# ESL_EMITTER.net
KiCad netlist of a schematic drawn in EAGLE
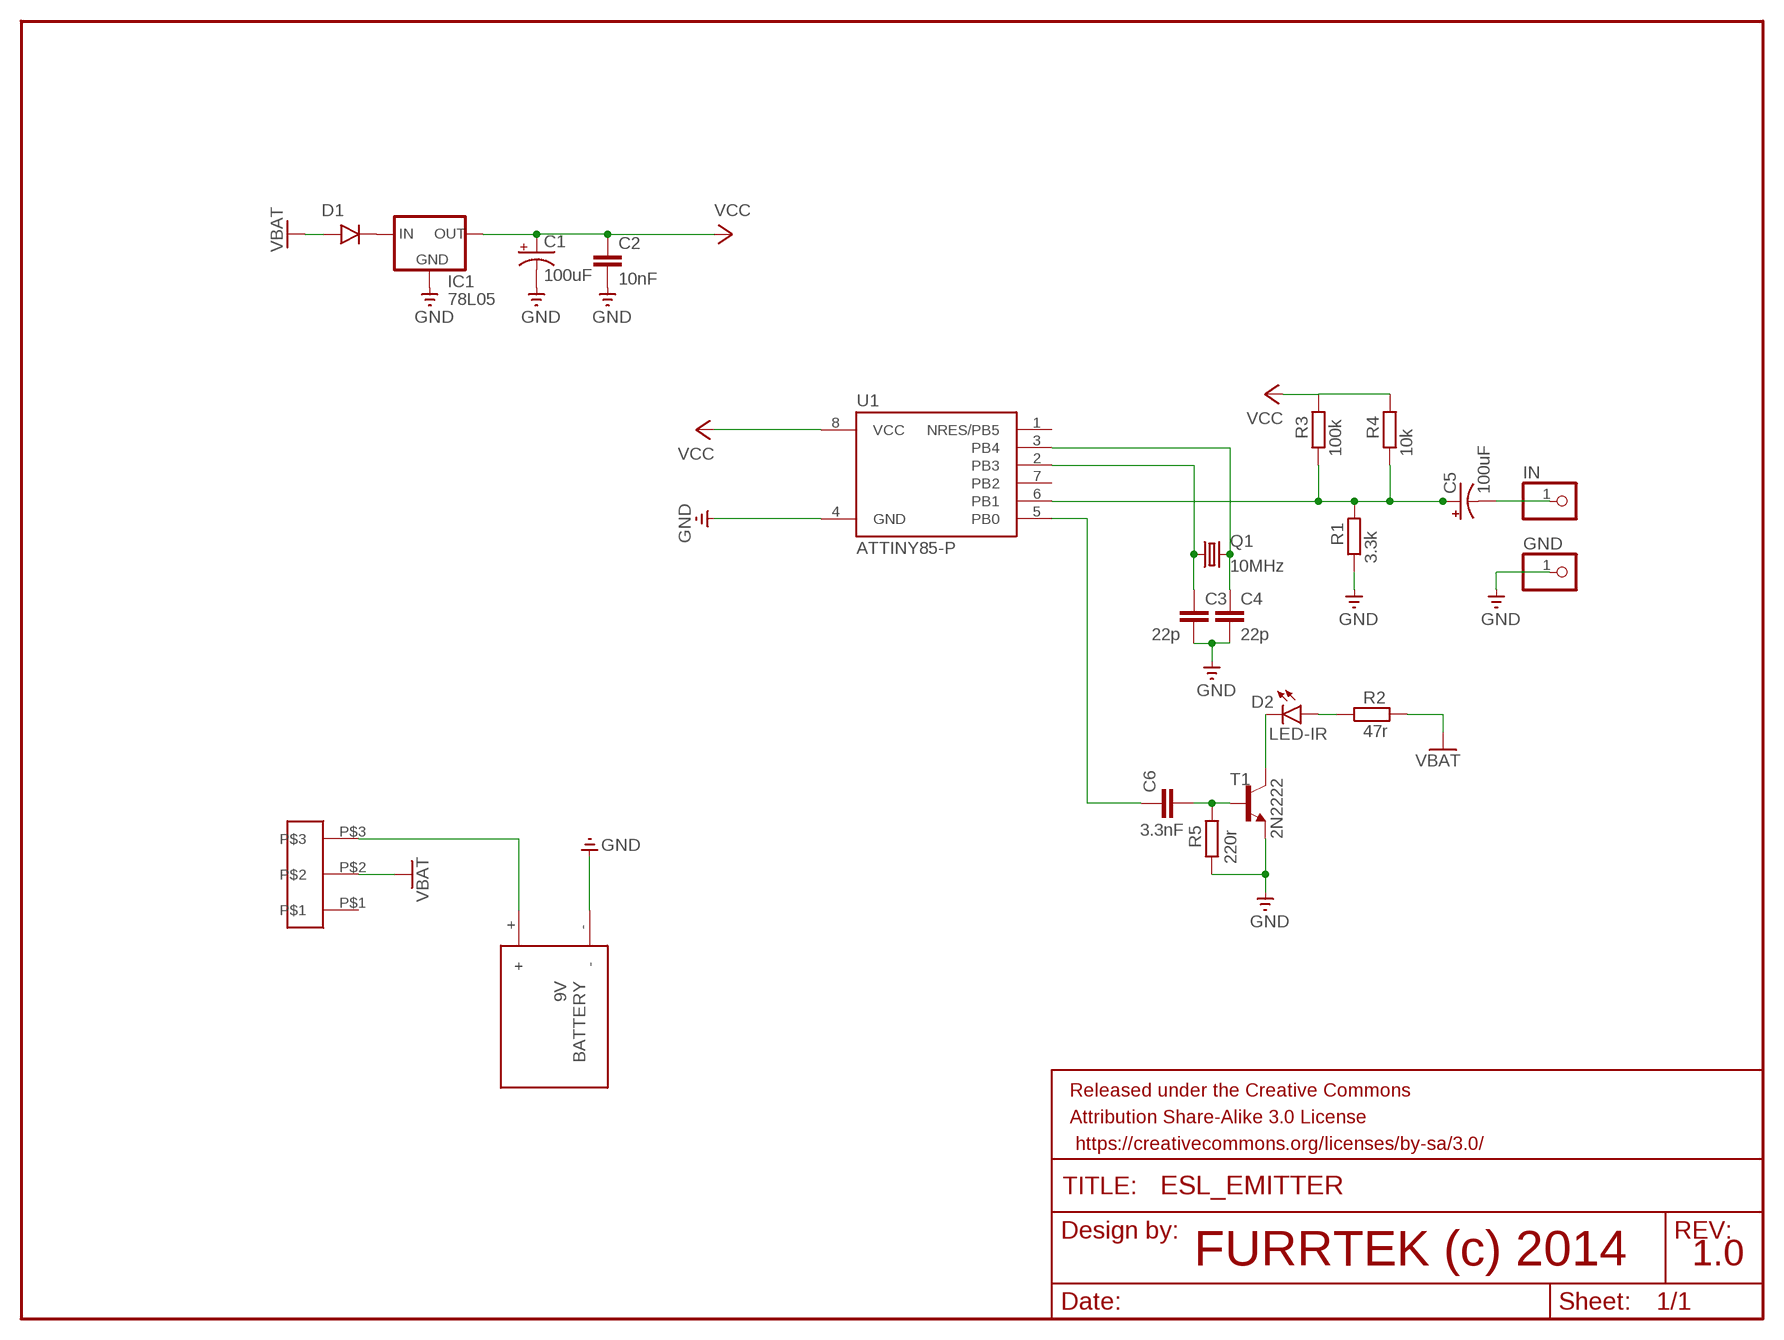
[diagram p0: schematic, sheet 1]

(export (version "E")
  (design (tool "Eeschema 10.0.6"))
  (components
    (comp (ref "C1")
      (value "100uF")
      (footprint "eagle-import:CPOL-RADIAL-10UF-25V")
      (libsource (lib "eagle-import") (part "CAP_POLPTH2"))
    )
    (comp (ref "C2")
      (value "10nF")
      (footprint "eagle-import:CAP-PTH-10MM")
      (libsource (lib "eagle-import") (part "10NF-PTH-10MM-10000V-1-%"))
    )
    (comp (ref "C3")
      (value "22p")
      (footprint "eagle-import:CAP-PTH-10MM")
      (libsource (lib "eagle-import") (part "10NF-PTH-10MM-10000V-1-%"))
    )
    (comp (ref "C4")
      (value "22p")
      (footprint "eagle-import:CAP-PTH-10MM")
      (libsource (lib "eagle-import") (part "10NF-PTH-10MM-10000V-1-%"))
    )
    (comp (ref "C5")
      (value "100uF")
      (footprint "eagle-import:CPOL-RADIAL-10UF-25V")
      (libsource (lib "eagle-import") (part "CAP_POLPTH2"))
    )
    (comp (ref "C6")
      (value "3.3nF")
      (footprint "eagle-import:CAP-PTH-10MM")
      (libsource (lib "eagle-import") (part "10NF-PTH-10MM-10000V-1-%"))
    )
    (comp (ref "D1")
      (value "1N4001")
      (footprint "eagle-import:DO41-10")
      (libsource (lib "eagle-import") (part "1N4001"))
    )
    (comp (ref "D2")
      (value "LED-IR")
      (footprint "eagle-import:LED_3MM-NS")
      (libsource (lib "eagle-import") (part "LED-3MM-NO_SILK"))
    )
    (comp (ref "FRAME1")
      (value "FRAME-LETTER")
      (footprint "eagle-import:CREATIVE_COMMONS")
      (libsource (lib "eagle-import") (part "FRAME-LETTER"))
    )
    (comp (ref "GND")
      (value "PINHD-1X1")
      (footprint "eagle-import:1X01")
      (libsource (lib "eagle-import") (part "PINHD-1X1"))
    )
    (comp (ref "IC1")
      (value "78L05")
      (footprint "eagle-import:78XXL")
      (libsource (lib "eagle-import") (part "V_REG_78XXSIDE"))
    )
    (comp (ref "IN")
      (value "PINHD-1X1")
      (footprint "eagle-import:1X01")
      (libsource (lib "eagle-import") (part "PINHD-1X1"))
    )
    (comp (ref "Q1")
      (value "10MHz")
      (footprint "eagle-import:HC49U-H")
      (libsource (lib "eagle-import") (part "CRYSTALHC49U-H"))
    )
    (comp (ref "R1")
      (value "3.3k")
      (footprint "eagle-import:0207_7")
      (libsource (lib "eagle-import") (part "R-EU_0207/7"))
    )
    (comp (ref "R2")
      (value "47r")
      (footprint "eagle-import:0207_7")
      (libsource (lib "eagle-import") (part "R-EU_0207/7"))
    )
    (comp (ref "R3")
      (value "100k")
      (footprint "eagle-import:0207_7")
      (libsource (lib "eagle-import") (part "R-EU_0207/7"))
    )
    (comp (ref "R4")
      (value "10k")
      (footprint "eagle-import:0207_7")
      (libsource (lib "eagle-import") (part "R-EU_0207/7"))
    )
    (comp (ref "R5")
      (value "220r")
      (footprint "eagle-import:0207_7")
      (libsource (lib "eagle-import") (part "R-EU_0207/7"))
    )
    (comp (ref "T1")
      (value "2N2222")
      (footprint "eagle-import:TO92-EBC-OVAL")
      (libsource (lib "eagle-import") (part "2N2222"))
    )
    (comp (ref "U$2")
      (value "PACKAGESWITCH")
      (footprint "eagle-import:SLIDESWITCH")
      (libsource (lib "eagle-import") (part "PACKAGESWITCH"))
    )
    (comp (ref "U$3")
      (value "BAT")
      (footprint "eagle-import:BAT")
      (libsource (lib "eagle-import") (part "BAT"))
    )
    (comp (ref "U1")
      (value "ATTINY85-P")
      (footprint "eagle-import:PDIP08_300MIL")
      (libsource (lib "eagle-import") (part "ATTINY85P-"))
    )
  )
  (nets
    (net (code "1") (name "GND") (class "Default")
      (node (ref "C1") (pin "2") (pinfunction "-_2") (pintype "passive"))
      (node (ref "C2") (pin "2") (pinfunction "2_2") (pintype "passive"))
      (node (ref "C3") (pin "2") (pinfunction "2_2") (pintype "passive"))
      (node (ref "C4") (pin "2") (pinfunction "2_2") (pintype "passive"))
      (node (ref "GND") (pin "1") (pinfunction "1_1") (pintype "passive"))
      (node (ref "IC1") (pin "GND") (pinfunction "GND_GND") (pintype "input"))
      (node (ref "R1") (pin "1") (pinfunction "1_1") (pintype "passive"))
      (node (ref "R5") (pin "1") (pinfunction "1_1") (pintype "passive"))
      (node (ref "T1") (pin "E") (pinfunction "E_E") (pintype "passive"))
      (node (ref "U$3") (pin "-") (pinfunction "-_-") (pintype "bidirectional"))
      (node (ref "U1") (pin "4") (pinfunction "GND_4") (pintype "power_in"))
    )
    (net (code "2") (name "Net-(C5-+)") (class "Default")
      (node (ref "C5") (pin "1") (pinfunction "+_1") (pintype "passive"))
      (node (ref "R1") (pin "2") (pinfunction "2_2") (pintype "passive"))
      (node (ref "R3") (pin "1") (pinfunction "1_1") (pintype "passive"))
      (node (ref "R4") (pin "1") (pinfunction "1_1") (pintype "passive"))
      (node (ref "U1") (pin "6") (pinfunction "PB1_6") (pintype "bidirectional"))
    )
    (net (code "3") (name "Net-(C5--)") (class "Default")
      (node (ref "C5") (pin "2") (pinfunction "-_2") (pintype "passive"))
      (node (ref "IN") (pin "1") (pinfunction "1_1") (pintype "passive"))
    )
    (net (code "4") (name "Net-(C6-Pad2)") (class "Default")
      (node (ref "C6") (pin "2") (pinfunction "2_2") (pintype "passive"))
      (node (ref "R5") (pin "2") (pinfunction "2_2") (pintype "passive"))
      (node (ref "T1") (pin "B") (pinfunction "B_B") (pintype "passive"))
    )
    (net (code "5") (name "Net-(D1-CATHODE)") (class "Default")
      (node (ref "D1") (pin "C") (pinfunction "CATHODE_C") (pintype "passive"))
      (node (ref "IC1") (pin "IN") (pinfunction "IN_IN") (pintype "input"))
    )
    (net (code "6") (name "Net-(D2-C)") (class "Default")
      (node (ref "D2") (pin "K") (pinfunction "C_K") (pintype "passive"))
      (node (ref "T1") (pin "C") (pinfunction "C_C") (pintype "passive"))
    )
    (net (code "7") (name "Net-(D2-PadA)") (class "Default")
      (node (ref "D2") (pin "A") (pinfunction "A_A") (pintype "passive"))
      (node (ref "R2") (pin "1") (pinfunction "1_1") (pintype "passive"))
    )
    (net (code "8") (name "Net-(U$2-PadP$3)") (class "Default")
      (node (ref "U$2") (pin "P$3") (pinfunction "P$3_P$3") (pintype "bidirectional"))
      (node (ref "U$3") (pin "+") (pinfunction "+_+") (pintype "bidirectional"))
    )
    (net (code "9") (name "Net-(U1-PB0)") (class "Default")
      (node (ref "C6") (pin "1") (pinfunction "1_1") (pintype "passive"))
      (node (ref "U1") (pin "5") (pinfunction "PB0_5") (pintype "bidirectional"))
    )
    (net (code "10") (name "Net-(U1-PB3)") (class "Default")
      (node (ref "C3") (pin "1") (pinfunction "1_1") (pintype "passive"))
      (node (ref "Q1") (pin "1") (pinfunction "1_1") (pintype "passive"))
      (node (ref "U1") (pin "2") (pinfunction "PB3_2") (pintype "bidirectional"))
    )
    (net (code "11") (name "Net-(U1-PB4)") (class "Default")
      (node (ref "C4") (pin "1") (pinfunction "1_1") (pintype "passive"))
      (node (ref "Q1") (pin "2") (pinfunction "2_2") (pintype "passive"))
      (node (ref "U1") (pin "3") (pinfunction "PB4_3") (pintype "bidirectional"))
    )
    (net (code "12") (name "VBAT") (class "Default")
      (node (ref "D1") (pin "A") (pinfunction "ANODE_A") (pintype "passive"))
      (node (ref "R2") (pin "2") (pinfunction "2_2") (pintype "passive"))
      (node (ref "U$2") (pin "P$2") (pinfunction "P$2_P$2") (pintype "bidirectional"))
    )
    (net (code "13") (name "VCC") (class "Default")
      (node (ref "C1") (pin "1") (pinfunction "+_1") (pintype "passive"))
      (node (ref "C2") (pin "1") (pinfunction "1_1") (pintype "passive"))
      (node (ref "IC1") (pin "OUT") (pinfunction "OUT_OUT") (pintype "output"))
      (node (ref "R3") (pin "2") (pinfunction "2_2") (pintype "passive"))
      (node (ref "R4") (pin "2") (pinfunction "2_2") (pintype "passive"))
      (node (ref "U1") (pin "8") (pinfunction "VCC_8") (pintype "power_in"))
    )
    (net (code "14") (name "unconnected-(U$2-PadP$1)") (class "Default")
      (node (ref "U$2") (pin "P$1") (pinfunction "P$1_P$1") (pintype "bidirectional"))
    )
    (net (code "15") (name "unconnected-(U1-NRES{slash}PB5-Pad1)") (class "Default")
      (node (ref "U1") (pin "1") (pinfunction "NRES/PB5_1") (pintype "bidirectional"))
    )
    (net (code "16") (name "unconnected-(U1-PB2-Pad7)") (class "Default")
      (node (ref "U1") (pin "7") (pinfunction "PB2_7") (pintype "bidirectional"))
    )
  )
)
